# LightMod.net
KiCad netlist of a schematic drawn in Altium Designer
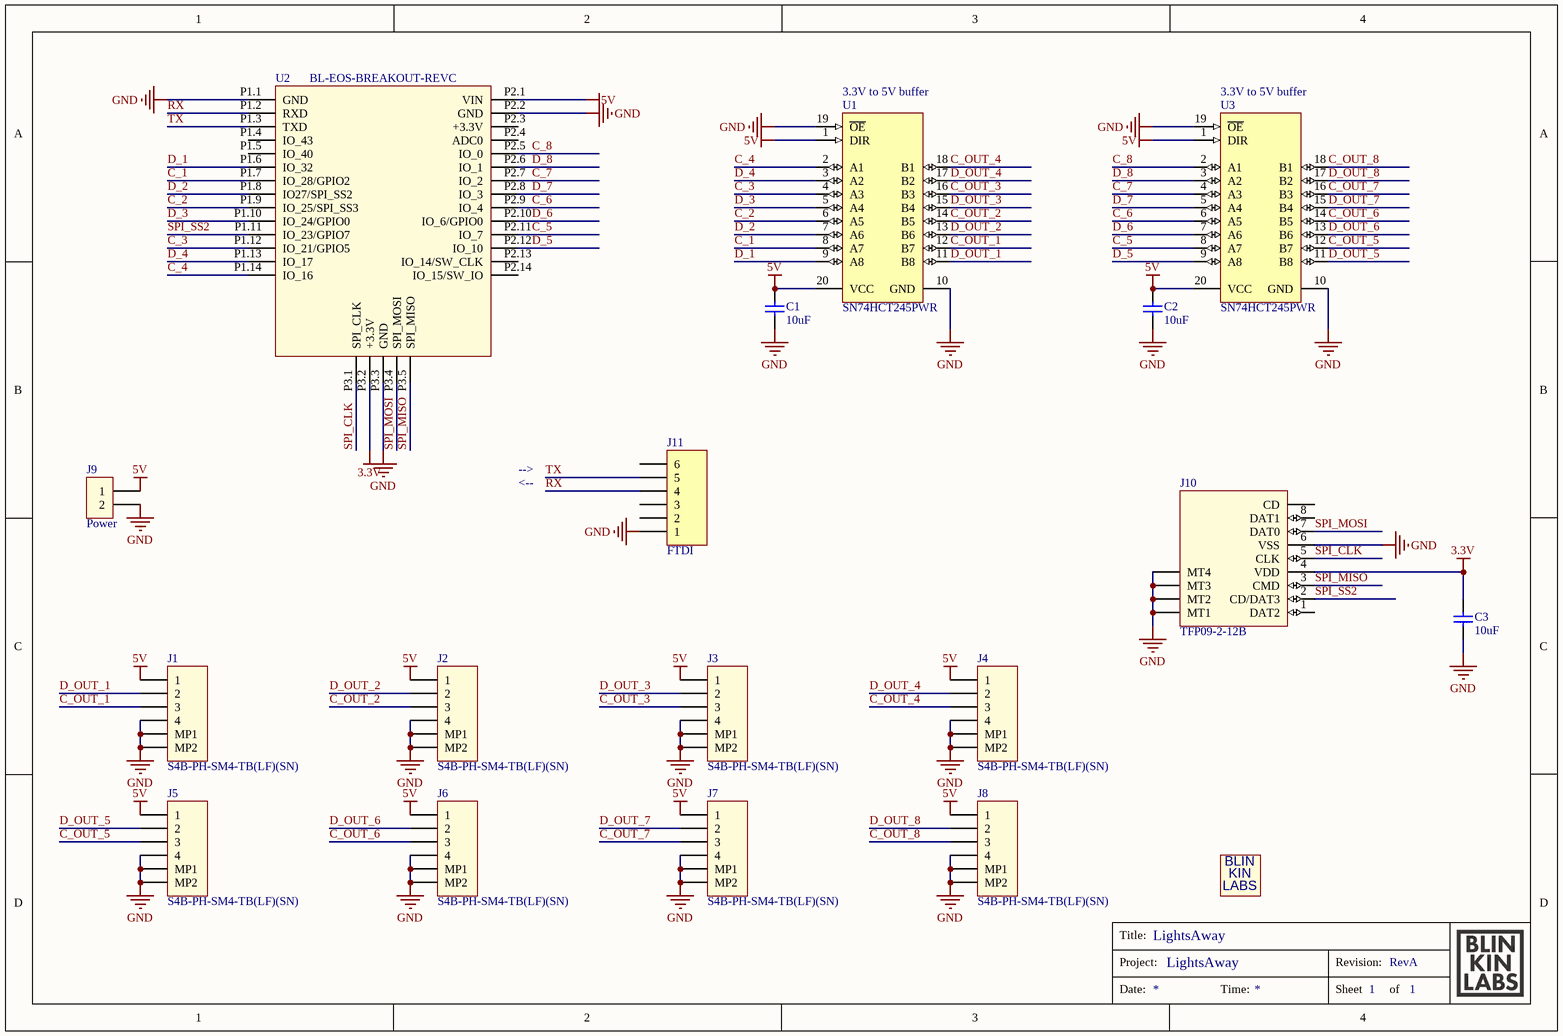
[diagram p0: LightMod.SchDoc]

(export (version "E")
  (design (tool "Eeschema 10.0.6"))
  (components
    (comp (ref "C1")
      (value "10uF")
      (footprint "CAPC2012X10N")
      (description "CAP CER 10UF 16V X5R 0805")
      (fields
        (field (name "DIGI-KEY PART NUMBER") "490-6474-1-ND")
        (field (name "MANUFACTURER") "Murata Electronics North America")
      )
      (libsource (lib "cap_murata") (part "CAPACITOR"))
    )
    (comp (ref "C2")
      (value "10uF")
      (footprint "CAPC2012X10N")
      (description "CAP CER 10UF 16V X5R 0805")
      (fields
        (field (name "DIGI-KEY PART NUMBER") "490-6474-1-ND")
        (field (name "MANUFACTURER") "Murata Electronics North America")
      )
      (libsource (lib "cap_murata") (part "CAPACITOR"))
    )
    (comp (ref "C3")
      (value "10uF")
      (footprint "CAPC2012X10N")
      (description "CAP CER 10UF 16V X5R 0805")
      (fields
        (field (name "DIGI-KEY PART NUMBER") "490-6474-1-ND")
        (field (name "MANUFACTURER") "Murata Electronics North America")
      )
      (libsource (lib "cap_murata") (part "CAPACITOR"))
    )
    (comp (ref "J1")
      (value "S4B-PH-SM4-TB(LF)(SN)")
      (footprint "S4B-PH-SM4-TB(LF)(SN)")
      (description "CONN HEADER SMD R/A 4POS 2MM")
      (fields (field (name "MANUFACTURER") "JST"))
      (libsource (lib "Blinkinlabs") (part "S4B-PH-SM4-TB(LF)(SN)"))
    )
    (comp (ref "J2")
      (value "S4B-PH-SM4-TB(LF)(SN)")
      (footprint "S4B-PH-SM4-TB(LF)(SN)")
      (description "CONN HEADER SMD R/A 4POS 2MM")
      (fields (field (name "MANUFACTURER") "JST"))
      (libsource (lib "Blinkinlabs") (part "S4B-PH-SM4-TB(LF)(SN)"))
    )
    (comp (ref "J3")
      (value "S4B-PH-SM4-TB(LF)(SN)")
      (footprint "S4B-PH-SM4-TB(LF)(SN)")
      (description "CONN HEADER SMD R/A 4POS 2MM")
      (fields (field (name "MANUFACTURER") "JST"))
      (libsource (lib "Blinkinlabs") (part "S4B-PH-SM4-TB(LF)(SN)"))
    )
    (comp (ref "J4")
      (value "S4B-PH-SM4-TB(LF)(SN)")
      (footprint "S4B-PH-SM4-TB(LF)(SN)")
      (description "CONN HEADER SMD R/A 4POS 2MM")
      (fields (field (name "MANUFACTURER") "JST"))
      (libsource (lib "Blinkinlabs") (part "S4B-PH-SM4-TB(LF)(SN)"))
    )
    (comp (ref "J5")
      (value "S4B-PH-SM4-TB(LF)(SN)")
      (footprint "S4B-PH-SM4-TB(LF)(SN)")
      (description "CONN HEADER SMD R/A 4POS 2MM")
      (fields (field (name "MANUFACTURER") "JST"))
      (libsource (lib "Blinkinlabs") (part "S4B-PH-SM4-TB(LF)(SN)"))
    )
    (comp (ref "J6")
      (value "S4B-PH-SM4-TB(LF)(SN)")
      (footprint "S4B-PH-SM4-TB(LF)(SN)")
      (description "CONN HEADER SMD R/A 4POS 2MM")
      (fields (field (name "MANUFACTURER") "JST"))
      (libsource (lib "Blinkinlabs") (part "S4B-PH-SM4-TB(LF)(SN)"))
    )
    (comp (ref "J7")
      (value "S4B-PH-SM4-TB(LF)(SN)")
      (footprint "S4B-PH-SM4-TB(LF)(SN)")
      (description "CONN HEADER SMD R/A 4POS 2MM")
      (fields (field (name "MANUFACTURER") "JST"))
      (libsource (lib "Blinkinlabs") (part "S4B-PH-SM4-TB(LF)(SN)"))
    )
    (comp (ref "J8")
      (value "S4B-PH-SM4-TB(LF)(SN)")
      (footprint "S4B-PH-SM4-TB(LF)(SN)")
      (description "CONN HEADER SMD R/A 4POS 2MM")
      (fields (field (name "MANUFACTURER") "JST"))
      (libsource (lib "Blinkinlabs") (part "S4B-PH-SM4-TB(LF)(SN)"))
    )
    (comp (ref "J9")
      (value "Power")
      (footprint "1751248")
      (description "TERM BLK 2POS SIDE ENT 3.5MM PCB")
      (fields (field (name "MANUFACTURER") "Phoenix Contact") (field (name "PARTNUMBER") "1751248"))
      (libsource (lib "Blinkinlabs") (part "1751248"))
    )
    (comp (ref "J10")
      (value "TFP09-2-12B")
      (footprint "TFP09-2-12B")
      (description "Micro SD Card Connector")
      (fields (field (name "MANUFACTURER") "Unknown/Generic"))
      (libsource (lib "Blinkinlabs") (part "TFP09-2-12B"))
    )
    (comp (ref "J11")
      (value "FTDI")
      (footprint "HDR1X6")
      (description "Header, 6-Pin")
      (fields (field (name "PUBLISHER") "Altium Limited"))
      (libsource (lib "Miscellaneous Connectors") (part "Header 6"))
    )
    (comp (ref "L1")
      (value "BLINKINLABS_LOGO")
      (footprint "BLINKINLABS_LOGO")
      (description "Square logo")
      (libsource (lib "Blinkinlabs") (part "BLINKINLABS_LOGO"))
    )
    (comp (ref "U1")
      (value "SN74HCT245PWR")
      (footprint "PW0020A_L")
      (description "Octal Bus Transceivers With 3-State Outputs, PW0020A, LARGE T&R")
      (fields
        (field (name "MANUFACTURER") "Texas Instruments")
        (field (name "GENERIC PART NUMBER") "SN74HCT245")
      )
      (libsource (lib "Altium Content Vault") (part "TI-SN_CDX4XXXXXX245XX_6XXX-20"))
    )
    (comp (ref "U2")
      (value "BL-EOS-BREAKOUT-REVC")
      (footprint "BL-EOS-BREAKOUT-REVC")
      (fields (field (name "MANUFACTURER") "Blinkinlabs") (field (name "PARTNUMBER") "QL-EOS-S3-Breakout"))
      (libsource (lib "Blinkinlabs") (part "BL-EOS-BREAKOUT-REVC"))
    )
    (comp (ref "U3")
      (value "SN74HCT245PWR")
      (footprint "PW0020A_L")
      (description "Octal Bus Transceivers With 3-State Outputs, PW0020A, LARGE T&R")
      (fields
        (field (name "MANUFACTURER") "Texas Instruments")
        (field (name "GENERIC PART NUMBER") "SN74HCT245")
      )
      (libsource (lib "Altium Content Vault") (part "TI-SN_CDX4XXXXXX245XX_6XXX-20"))
    )
  )
  (nets
    (net (code "1") (name "/C_1") (class "Default")
      (node (ref "U1") (pin "8") (pinfunction "A7_8") (pintype "bidirectional"))
      (node (ref "U2") (pin "P1.7") (pinfunction "IO_28/GPIO2_P1.7") (pintype "passive"))
    )
    (net (code "2") (name "/C_2") (class "Default")
      (node (ref "U1") (pin "6") (pinfunction "A5_6") (pintype "bidirectional"))
      (node (ref "U2") (pin "P1.9") (pinfunction "IO_25/SPI_SS3_P1.9") (pintype "passive"))
    )
    (net (code "3") (name "/C_3") (class "Default")
      (node (ref "U1") (pin "4") (pinfunction "A3_4") (pintype "bidirectional"))
      (node (ref "U2") (pin "P1.12") (pinfunction "IO_21/GPIO5_P1.12") (pintype "passive"))
    )
    (net (code "4") (name "/C_4") (class "Default")
      (node (ref "U1") (pin "2") (pinfunction "A1_2") (pintype "bidirectional"))
      (node (ref "U2") (pin "P1.14") (pinfunction "IO_16_P1.14") (pintype "passive"))
    )
    (net (code "5") (name "/C_5") (class "Default")
      (node (ref "U2") (pin "P2.11") (pinfunction "IO_7_P2.11") (pintype "passive"))
      (node (ref "U3") (pin "8") (pinfunction "A7_8") (pintype "bidirectional"))
    )
    (net (code "6") (name "/C_6") (class "Default")
      (node (ref "U2") (pin "P2.9") (pinfunction "IO_4_P2.9") (pintype "passive"))
      (node (ref "U3") (pin "6") (pinfunction "A5_6") (pintype "bidirectional"))
    )
    (net (code "7") (name "/C_7") (class "Default")
      (node (ref "U2") (pin "P2.7") (pinfunction "IO_2_P2.7") (pintype "passive"))
      (node (ref "U3") (pin "4") (pinfunction "A3_4") (pintype "bidirectional"))
    )
    (net (code "8") (name "/C_8") (class "Default")
      (node (ref "U2") (pin "P2.5") (pinfunction "IO_0_P2.5") (pintype "passive"))
      (node (ref "U3") (pin "2") (pinfunction "A1_2") (pintype "bidirectional"))
    )
    (net (code "9") (name "/C_OUT_1") (class "Default")
      (node (ref "J1") (pin "3") (pinfunction "3_3") (pintype "passive"))
      (node (ref "U1") (pin "12") (pinfunction "B7_12") (pintype "bidirectional"))
    )
    (net (code "10") (name "/C_OUT_2") (class "Default")
      (node (ref "J2") (pin "3") (pinfunction "3_3") (pintype "passive"))
      (node (ref "U1") (pin "14") (pinfunction "B5_14") (pintype "bidirectional"))
    )
    (net (code "11") (name "/C_OUT_3") (class "Default")
      (node (ref "J3") (pin "3") (pinfunction "3_3") (pintype "passive"))
      (node (ref "U1") (pin "16") (pinfunction "B3_16") (pintype "bidirectional"))
    )
    (net (code "12") (name "/C_OUT_4") (class "Default")
      (node (ref "J4") (pin "3") (pinfunction "3_3") (pintype "passive"))
      (node (ref "U1") (pin "18") (pinfunction "B1_18") (pintype "bidirectional"))
    )
    (net (code "13") (name "/C_OUT_5") (class "Default")
      (node (ref "J5") (pin "3") (pinfunction "3_3") (pintype "passive"))
      (node (ref "U3") (pin "12") (pinfunction "B7_12") (pintype "bidirectional"))
    )
    (net (code "14") (name "/C_OUT_6") (class "Default")
      (node (ref "J6") (pin "3") (pinfunction "3_3") (pintype "passive"))
      (node (ref "U3") (pin "14") (pinfunction "B5_14") (pintype "bidirectional"))
    )
    (net (code "15") (name "/C_OUT_7") (class "Default")
      (node (ref "J7") (pin "3") (pinfunction "3_3") (pintype "passive"))
      (node (ref "U3") (pin "16") (pinfunction "B3_16") (pintype "bidirectional"))
    )
    (net (code "16") (name "/C_OUT_8") (class "Default")
      (node (ref "J8") (pin "3") (pinfunction "3_3") (pintype "passive"))
      (node (ref "U3") (pin "18") (pinfunction "B1_18") (pintype "bidirectional"))
    )
    (net (code "17") (name "/D_1") (class "Default")
      (node (ref "U1") (pin "9") (pinfunction "A8_9") (pintype "bidirectional"))
      (node (ref "U2") (pin "P1.6") (pinfunction "IO_32_P1.6") (pintype "passive"))
    )
    (net (code "18") (name "/D_2") (class "Default")
      (node (ref "U1") (pin "7") (pinfunction "A6_7") (pintype "bidirectional"))
      (node (ref "U2") (pin "P1.8") (pinfunction "IO27/SPI_SS2_P1.8") (pintype "passive"))
    )
    (net (code "19") (name "/D_3") (class "Default")
      (node (ref "U1") (pin "5") (pinfunction "A4_5") (pintype "bidirectional"))
      (node (ref "U2") (pin "P1.10") (pinfunction "IO_24/GPIO0_P1.10") (pintype "passive"))
    )
    (net (code "20") (name "/D_4") (class "Default")
      (node (ref "U1") (pin "3") (pinfunction "A2_3") (pintype "bidirectional"))
      (node (ref "U2") (pin "P1.13") (pinfunction "IO_17_P1.13") (pintype "passive"))
    )
    (net (code "21") (name "/D_5") (class "Default")
      (node (ref "U2") (pin "P2.12") (pinfunction "IO_10_P2.12") (pintype "passive"))
      (node (ref "U3") (pin "9") (pinfunction "A8_9") (pintype "bidirectional"))
    )
    (net (code "22") (name "/D_6") (class "Default")
      (node (ref "U2") (pin "P2.10") (pinfunction "IO_6/GPIO0_P2.10") (pintype "passive"))
      (node (ref "U3") (pin "7") (pinfunction "A6_7") (pintype "bidirectional"))
    )
    (net (code "23") (name "/D_7") (class "Default")
      (node (ref "U2") (pin "P2.8") (pinfunction "IO_3_P2.8") (pintype "passive"))
      (node (ref "U3") (pin "5") (pinfunction "A4_5") (pintype "bidirectional"))
    )
    (net (code "24") (name "/D_8") (class "Default")
      (node (ref "U2") (pin "P2.6") (pinfunction "IO_1_P2.6") (pintype "passive"))
      (node (ref "U3") (pin "3") (pinfunction "A2_3") (pintype "bidirectional"))
    )
    (net (code "25") (name "/D_OUT_1") (class "Default")
      (node (ref "J1") (pin "2") (pinfunction "2_2") (pintype "passive"))
      (node (ref "U1") (pin "11") (pinfunction "B8_11") (pintype "bidirectional"))
    )
    (net (code "26") (name "/D_OUT_2") (class "Default")
      (node (ref "J2") (pin "2") (pinfunction "2_2") (pintype "passive"))
      (node (ref "U1") (pin "13") (pinfunction "B6_13") (pintype "bidirectional"))
    )
    (net (code "27") (name "/D_OUT_3") (class "Default")
      (node (ref "J3") (pin "2") (pinfunction "2_2") (pintype "passive"))
      (node (ref "U1") (pin "15") (pinfunction "B4_15") (pintype "bidirectional"))
    )
    (net (code "28") (name "/D_OUT_4") (class "Default")
      (node (ref "J4") (pin "2") (pinfunction "2_2") (pintype "passive"))
      (node (ref "U1") (pin "17") (pinfunction "B2_17") (pintype "bidirectional"))
    )
    (net (code "29") (name "/D_OUT_5") (class "Default")
      (node (ref "J5") (pin "2") (pinfunction "2_2") (pintype "passive"))
      (node (ref "U3") (pin "11") (pinfunction "B8_11") (pintype "bidirectional"))
    )
    (net (code "30") (name "/D_OUT_6") (class "Default")
      (node (ref "J6") (pin "2") (pinfunction "2_2") (pintype "passive"))
      (node (ref "U3") (pin "13") (pinfunction "B6_13") (pintype "bidirectional"))
    )
    (net (code "31") (name "/D_OUT_7") (class "Default")
      (node (ref "J7") (pin "2") (pinfunction "2_2") (pintype "passive"))
      (node (ref "U3") (pin "15") (pinfunction "B4_15") (pintype "bidirectional"))
    )
    (net (code "32") (name "/D_OUT_8") (class "Default")
      (node (ref "J8") (pin "2") (pinfunction "2_2") (pintype "passive"))
      (node (ref "U3") (pin "17") (pinfunction "B2_17") (pintype "bidirectional"))
    )
    (net (code "33") (name "/RX") (class "Default")
      (node (ref "J11") (pin "4") (pinfunction "4_4") (pintype "passive"))
      (node (ref "U2") (pin "P1.2") (pinfunction "RXD_P1.2") (pintype "passive"))
    )
    (net (code "34") (name "/SPI_CLK") (class "Default")
      (node (ref "J10") (pin "5") (pinfunction "CLK_5") (pintype "bidirectional"))
      (node (ref "U2") (pin "P3.1") (pinfunction "SPI_CLK_P3.1") (pintype "passive"))
    )
    (net (code "35") (name "/SPI_MISO") (class "Default")
      (node (ref "J10") (pin "3") (pinfunction "CMD_3") (pintype "bidirectional"))
      (node (ref "U2") (pin "P3.5") (pinfunction "SPI_MISO_P3.5") (pintype "passive"))
    )
    (net (code "36") (name "/SPI_MOSI") (class "Default")
      (node (ref "J10") (pin "7") (pinfunction "DAT0_7") (pintype "bidirectional"))
      (node (ref "U2") (pin "P3.4") (pinfunction "SPI_MOSI_P3.4") (pintype "passive"))
    )
    (net (code "37") (name "/SPI_SS2") (class "Default")
      (node (ref "J10") (pin "2") (pinfunction "CD/DAT3_2") (pintype "bidirectional"))
      (node (ref "U2") (pin "P1.11") (pinfunction "IO_23/GPIO7_P1.11") (pintype "passive"))
    )
    (net (code "38") (name "/TX") (class "Default")
      (node (ref "J11") (pin "5") (pinfunction "5_5") (pintype "passive"))
      (node (ref "U2") (pin "P1.3") (pinfunction "TXD_P1.3") (pintype "passive"))
    )
    (net (code "39") (name "3.3V") (class "Default")
      (node (ref "C3") (pin "2") (pinfunction "2_2") (pintype "passive"))
      (node (ref "J10") (pin "4") (pinfunction "VDD_4") (pintype "power_in"))
      (node (ref "U2") (pin "P3.2") (pinfunction "+3.3V_P3.2") (pintype "passive"))
    )
    (net (code "40") (name "5V") (class "Default")
      (node (ref "C1") (pin "2") (pinfunction "2_2") (pintype "passive"))
      (node (ref "C2") (pin "2") (pinfunction "2_2") (pintype "passive"))
      (node (ref "J1") (pin "1") (pinfunction "1_1") (pintype "passive"))
      (node (ref "J2") (pin "1") (pinfunction "1_1") (pintype "passive"))
      (node (ref "J3") (pin "1") (pinfunction "1_1") (pintype "passive"))
      (node (ref "J4") (pin "1") (pinfunction "1_1") (pintype "passive"))
      (node (ref "J5") (pin "1") (pinfunction "1_1") (pintype "passive"))
      (node (ref "J6") (pin "1") (pinfunction "1_1") (pintype "passive"))
      (node (ref "J7") (pin "1") (pinfunction "1_1") (pintype "passive"))
      (node (ref "J8") (pin "1") (pinfunction "1_1") (pintype "passive"))
      (node (ref "J9") (pin "1") (pinfunction "1_1") (pintype "passive"))
      (node (ref "U1") (pin "1") (pinfunction "DIR_1") (pintype "input"))
      (node (ref "U1") (pin "20") (pinfunction "VCC_20") (pintype "power_in"))
      (node (ref "U2") (pin "P2.1") (pinfunction "VIN_P2.1") (pintype "passive"))
      (node (ref "U3") (pin "1") (pinfunction "DIR_1") (pintype "input"))
      (node (ref "U3") (pin "20") (pinfunction "VCC_20") (pintype "power_in"))
    )
    (net (code "41") (name "GND") (class "Default")
      (node (ref "C1") (pin "1") (pinfunction "1_1") (pintype "passive"))
      (node (ref "C2") (pin "1") (pinfunction "1_1") (pintype "passive"))
      (node (ref "C3") (pin "1") (pinfunction "1_1") (pintype "passive"))
      (node (ref "J1") (pin "4") (pinfunction "4_4") (pintype "passive"))
      (node (ref "J1") (pin "MP1") (pinfunction "MP1_MP1") (pintype "passive"))
      (node (ref "J1") (pin "MP2") (pinfunction "MP2_MP2") (pintype "passive"))
      (node (ref "J10") (pin "6") (pinfunction "VSS_6") (pintype "power_in"))
      (node (ref "J10") (pin "MT1") (pinfunction "MT1_MT1") (pintype "passive"))
      (node (ref "J10") (pin "MT2") (pinfunction "MT2_MT2") (pintype "passive"))
      (node (ref "J10") (pin "MT3") (pinfunction "MT3_MT3") (pintype "passive"))
      (node (ref "J10") (pin "MT4") (pinfunction "MT4_MT4") (pintype "passive"))
      (node (ref "J11") (pin "1") (pinfunction "1_1") (pintype "passive"))
      (node (ref "J2") (pin "4") (pinfunction "4_4") (pintype "passive"))
      (node (ref "J2") (pin "MP1") (pinfunction "MP1_MP1") (pintype "passive"))
      (node (ref "J2") (pin "MP2") (pinfunction "MP2_MP2") (pintype "passive"))
      (node (ref "J3") (pin "4") (pinfunction "4_4") (pintype "passive"))
      (node (ref "J3") (pin "MP1") (pinfunction "MP1_MP1") (pintype "passive"))
      (node (ref "J3") (pin "MP2") (pinfunction "MP2_MP2") (pintype "passive"))
      (node (ref "J4") (pin "4") (pinfunction "4_4") (pintype "passive"))
      (node (ref "J4") (pin "MP1") (pinfunction "MP1_MP1") (pintype "passive"))
      (node (ref "J4") (pin "MP2") (pinfunction "MP2_MP2") (pintype "passive"))
      (node (ref "J5") (pin "4") (pinfunction "4_4") (pintype "passive"))
      (node (ref "J5") (pin "MP1") (pinfunction "MP1_MP1") (pintype "passive"))
      (node (ref "J5") (pin "MP2") (pinfunction "MP2_MP2") (pintype "passive"))
      (node (ref "J6") (pin "4") (pinfunction "4_4") (pintype "passive"))
      (node (ref "J6") (pin "MP1") (pinfunction "MP1_MP1") (pintype "passive"))
      (node (ref "J6") (pin "MP2") (pinfunction "MP2_MP2") (pintype "passive"))
      (node (ref "J7") (pin "4") (pinfunction "4_4") (pintype "passive"))
      (node (ref "J7") (pin "MP1") (pinfunction "MP1_MP1") (pintype "passive"))
      (node (ref "J7") (pin "MP2") (pinfunction "MP2_MP2") (pintype "passive"))
      (node (ref "J8") (pin "4") (pinfunction "4_4") (pintype "passive"))
      (node (ref "J8") (pin "MP1") (pinfunction "MP1_MP1") (pintype "passive"))
      (node (ref "J8") (pin "MP2") (pinfunction "MP2_MP2") (pintype "passive"))
      (node (ref "J9") (pin "2") (pinfunction "2_2") (pintype "passive"))
      (node (ref "U1") (pin "10") (pinfunction "GND_10") (pintype "power_in"))
      (node (ref "U1") (pin "19") (pinfunction "~{OE}_19") (pintype "input"))
      (node (ref "U2") (pin "P1.1") (pinfunction "GND_P1.1") (pintype "passive"))
      (node (ref "U2") (pin "P2.2") (pinfunction "GND_P2.2") (pintype "passive"))
      (node (ref "U2") (pin "P3.3") (pinfunction "GND_P3.3") (pintype "passive"))
      (node (ref "U3") (pin "10") (pinfunction "GND_10") (pintype "power_in"))
      (node (ref "U3") (pin "19") (pinfunction "~{OE}_19") (pintype "input"))
    )
    (net (code "42") (name "unconnected-(J10-DAT1-Pad8)") (class "Default")
      (node (ref "J10") (pin "8") (pinfunction "DAT1_8") (pintype "bidirectional"))
    )
    (net (code "43") (name "unconnected-(J10-DAT2-Pad1)") (class "Default")
      (node (ref "J10") (pin "1") (pinfunction "DAT2_1") (pintype "bidirectional"))
    )
    (net (code "44") (name "unconnected-(J10-PadCD)") (class "Default")
      (node (ref "J10") (pin "CD") (pinfunction "CD_CD") (pintype "passive"))
    )
    (net (code "45") (name "unconnected-(J11-Pad2)") (class "Default")
      (node (ref "J11") (pin "2") (pinfunction "2_2") (pintype "passive"))
    )
    (net (code "46") (name "unconnected-(J11-Pad3)") (class "Default")
      (node (ref "J11") (pin "3") (pinfunction "3_3") (pintype "passive"))
    )
    (net (code "47") (name "unconnected-(J11-Pad6)") (class "Default")
      (node (ref "J11") (pin "6") (pinfunction "6_6") (pintype "passive"))
    )
    (net (code "48") (name "unconnected-(U2-+3.3V-PadP2.3)") (class "Default")
      (node (ref "U2") (pin "P2.3") (pinfunction "+3.3V_P2.3") (pintype "passive"))
    )
    (net (code "49") (name "unconnected-(U2-ADC0-PadP2.4)") (class "Default")
      (node (ref "U2") (pin "P2.4") (pinfunction "ADC0_P2.4") (pintype "passive"))
    )
    (net (code "50") (name "unconnected-(U2-IO_14{slash}SW_CLK-PadP2.13)") (class "Default")
      (node (ref "U2") (pin "P2.13") (pinfunction "IO_14/SW_CLK_P2.13") (pintype "passive"))
    )
    (net (code "51") (name "unconnected-(U2-IO_15{slash}SW_IO-PadP2.14)") (class "Default")
      (node (ref "U2") (pin "P2.14") (pinfunction "IO_15/SW_IO_P2.14") (pintype "passive"))
    )
    (net (code "52") (name "unconnected-(U2-IO_40-PadP1.5)") (class "Default")
      (node (ref "U2") (pin "P1.5") (pinfunction "IO_40_P1.5") (pintype "passive"))
    )
    (net (code "53") (name "unconnected-(U2-IO_43-PadP1.4)") (class "Default")
      (node (ref "U2") (pin "P1.4") (pinfunction "IO_43_P1.4") (pintype "passive"))
    )
  )
)
